# Eval.net
KiCad netlist of a schematic drawn in EAGLE
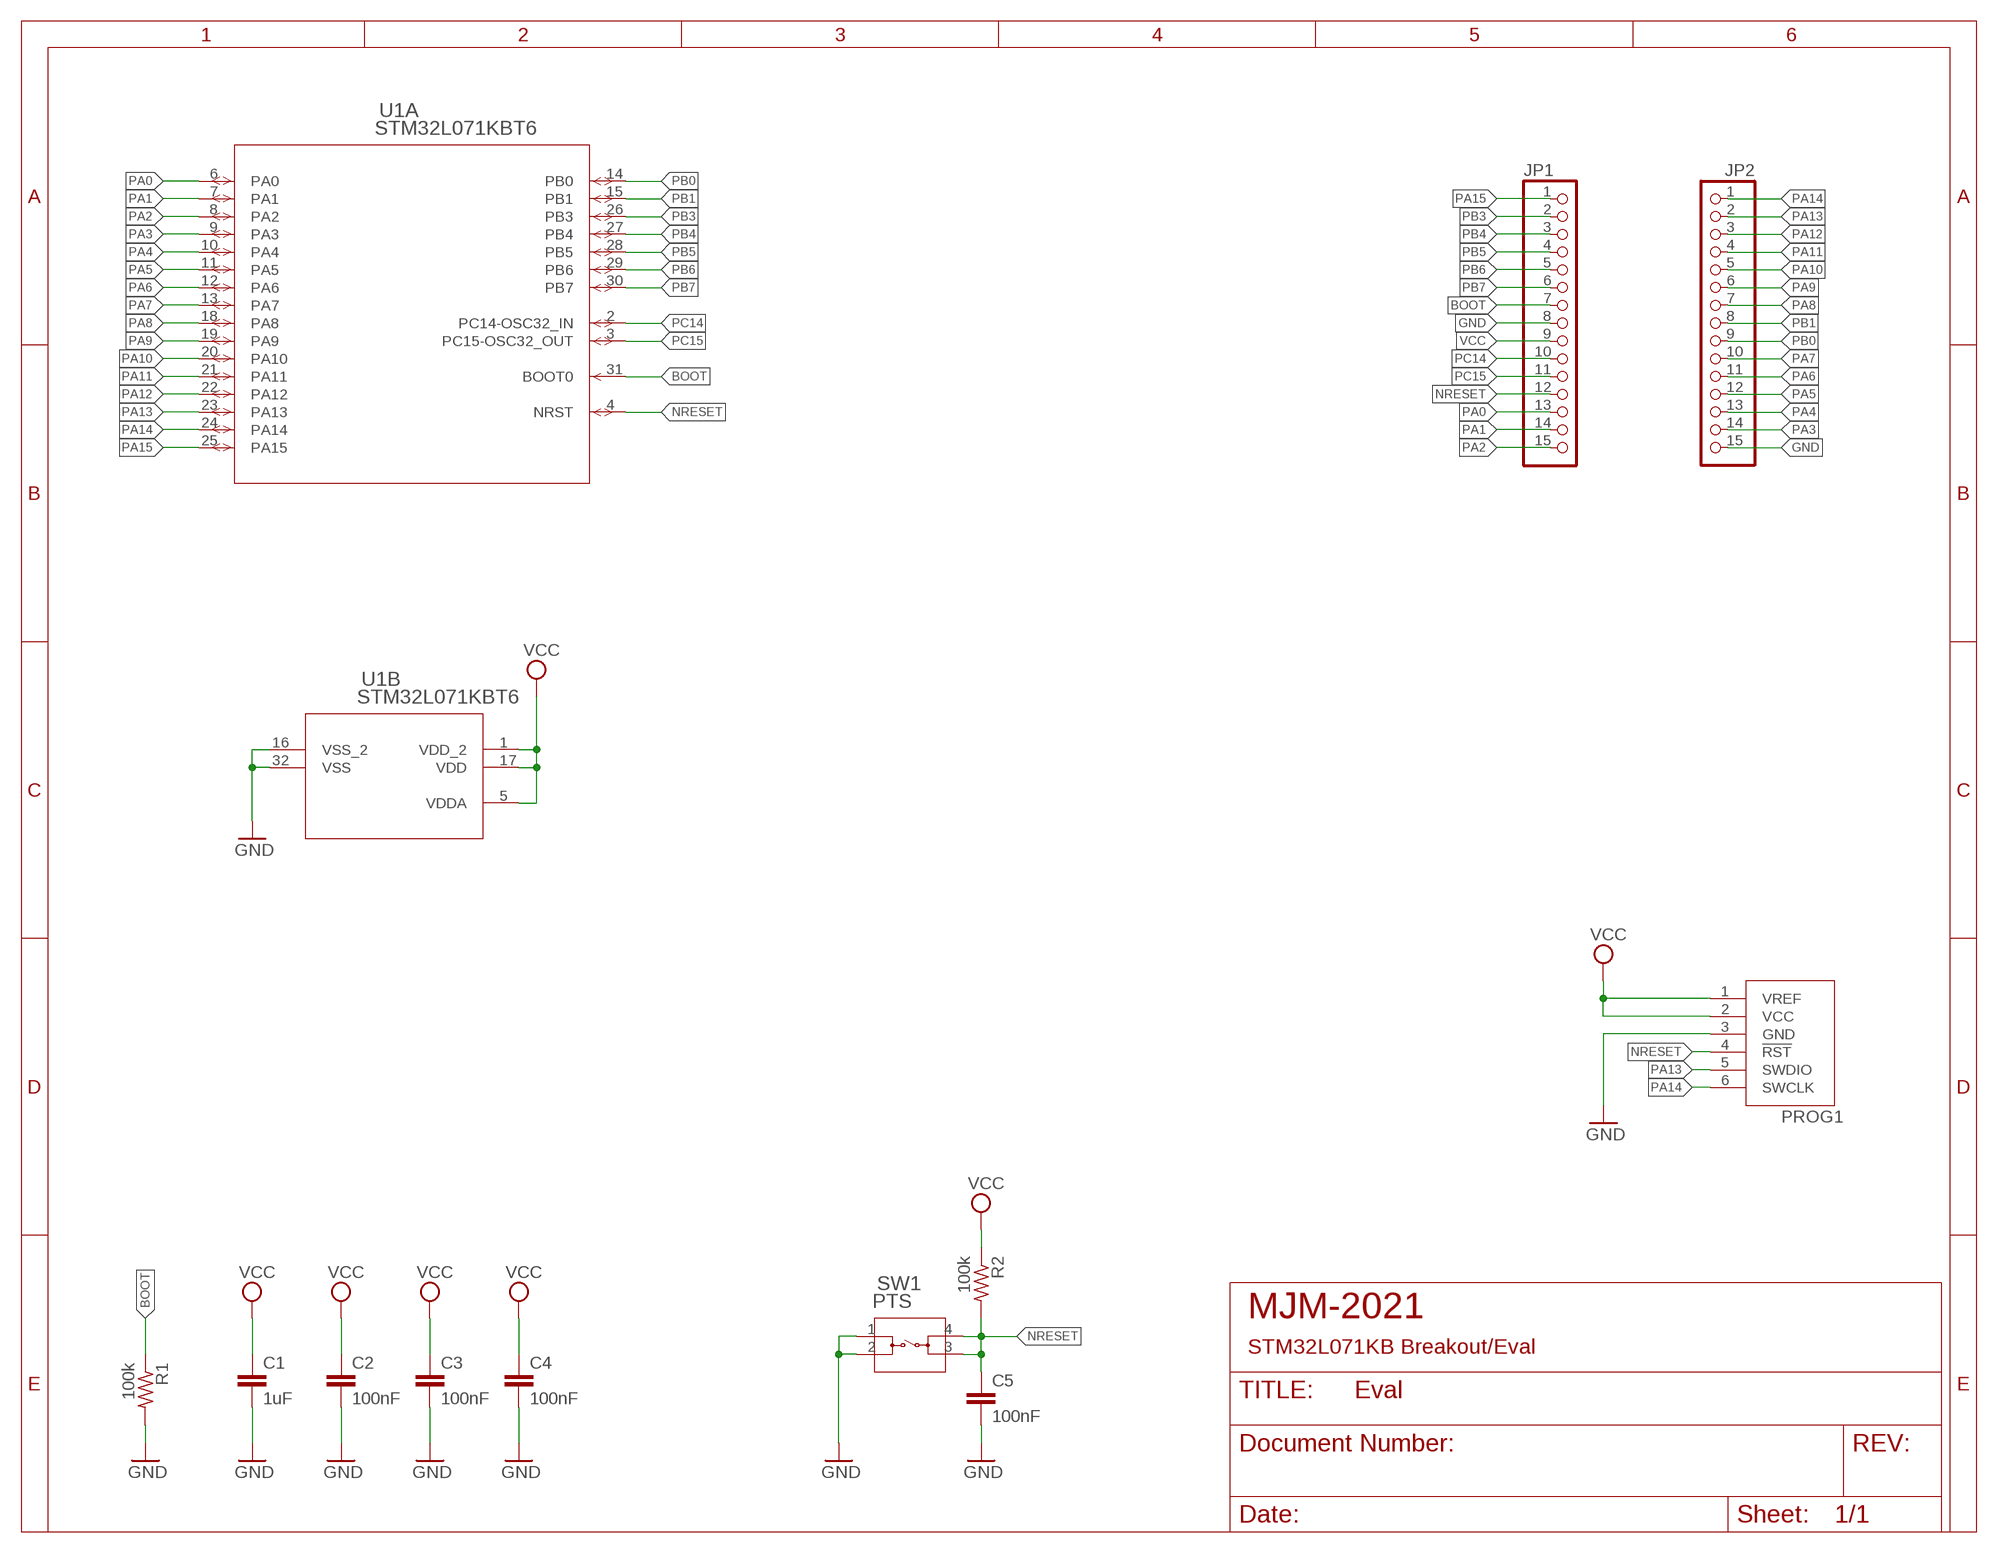
[diagram p0: schematic, sheet 1]

(export (version "E")
  (design (tool "Eeschema 10.0.6"))
  (components
    (comp (ref "C1")
      (value "1uF")
      (footprint "eagle-import:C0603")
      (libsource (lib "eagle-import") (part "C-EUC0603"))
    )
    (comp (ref "C2")
      (value "100nF")
      (footprint "eagle-import:C0603")
      (libsource (lib "eagle-import") (part "C-EUC0603"))
    )
    (comp (ref "C3")
      (value "100nF")
      (footprint "eagle-import:C0603")
      (libsource (lib "eagle-import") (part "C-EUC0603"))
    )
    (comp (ref "C4")
      (value "100nF")
      (footprint "eagle-import:C0603")
      (libsource (lib "eagle-import") (part "C-EUC0603"))
    )
    (comp (ref "C5")
      (value "100nF")
      (footprint "eagle-import:C0603")
      (libsource (lib "eagle-import") (part "C-EUC0603"))
    )
    (comp (ref "JP1")
      (value "PINHD-1X15")
      (footprint "eagle-import:1X15")
      (libsource (lib "eagle-import") (part "PINHD-1X15"))
    )
    (comp (ref "JP2")
      (value "PINHD-1X15")
      (footprint "eagle-import:1X15")
      (libsource (lib "eagle-import") (part "PINHD-1X15"))
    )
    (comp (ref "PROG1")
      (value "0532610671")
      (footprint "eagle-import:0532610671")
      (libsource (lib "eagle-import") (part "0532610671"))
    )
    (comp (ref "R1")
      (value "100k")
      (footprint "eagle-import:R0603")
      (libsource (lib "eagle-import") (part "R-US_R0603"))
    )
    (comp (ref "R2")
      (value "100k")
      (footprint "eagle-import:R0603")
      (libsource (lib "eagle-import") (part "R-US_R0603"))
    )
    (comp (ref "SW1")
      (value "PTS")
      (footprint "eagle-import:PTS_647_SN50_SMTR2_LFS-M")
      (fields
        (field (name "MANUFACTURER_PART_NUMBER") "PTS 647 SN50 SMTR2 LFS")
        (field (name "COPYRIGHT") "Copyright (C) 2018 Accelerated Designs. All rights reserved")
      )
      (libsource (lib "eagle-import") (part "PTS_647_SN50_SMTR2_LFSPTS_647_SN50_SMTR2_LFS-M"))
    )
    (comp (ref "U1")
      (value "STM32L071KBT6")
      (footprint "eagle-import:LQFP32_7X7X1P4")
      (fields (field (name "COPYRIGHT") "Copyright (C) 2018 Accelerated Designs. All rights reserved"))
      (libsource (lib "eagle-import") (part "STM32L071KBT6"))
    )
  )
  (nets
    (net (code "1") (name "BOOT") (class "Default")
      (node (ref "JP1") (pin "7") (pinfunction "7_7") (pintype "passive"))
      (node (ref "R1") (pin "1") (pinfunction "1_1") (pintype "passive"))
      (node (ref "U1") (pin "31") (pinfunction "BOOT0_31") (pintype "input"))
    )
    (net (code "2") (name "GND") (class "Default")
      (node (ref "C1") (pin "2") (pinfunction "2_2") (pintype "passive"))
      (node (ref "C2") (pin "2") (pinfunction "2_2") (pintype "passive"))
      (node (ref "C3") (pin "2") (pinfunction "2_2") (pintype "passive"))
      (node (ref "C4") (pin "2") (pinfunction "2_2") (pintype "passive"))
      (node (ref "C5") (pin "2") (pinfunction "2_2") (pintype "passive"))
      (node (ref "JP1") (pin "8") (pinfunction "8_8") (pintype "passive"))
      (node (ref "JP2") (pin "15") (pinfunction "15_15") (pintype "passive"))
      (node (ref "PROG1") (pin "3") (pinfunction "GND_3") (pintype "bidirectional"))
      (node (ref "R1") (pin "2") (pinfunction "2_2") (pintype "passive"))
      (node (ref "SW1") (pin "1") (pinfunction "1_1") (pintype "passive"))
      (node (ref "SW1") (pin "2") (pinfunction "2_2") (pintype "passive"))
      (node (ref "U1") (pin "16") (pinfunction "VSS_2_16") (pintype "power_in"))
      (node (ref "U1") (pin "32") (pinfunction "VSS_32") (pintype "power_in"))
    )
    (net (code "3") (name "NRESET") (class "Default")
      (node (ref "C5") (pin "1") (pinfunction "1_1") (pintype "passive"))
      (node (ref "JP1") (pin "12") (pinfunction "12_12") (pintype "passive"))
      (node (ref "PROG1") (pin "4") (pinfunction "~{RST}_4") (pintype "bidirectional"))
      (node (ref "R2") (pin "2") (pinfunction "2_2") (pintype "passive"))
      (node (ref "SW1") (pin "3") (pinfunction "3_3") (pintype "passive"))
      (node (ref "SW1") (pin "4") (pinfunction "4_4") (pintype "passive"))
      (node (ref "U1") (pin "4") (pinfunction "NRST_4") (pintype "bidirectional"))
    )
    (net (code "4") (name "PA0") (class "Default")
      (node (ref "JP1") (pin "13") (pinfunction "13_13") (pintype "passive"))
      (node (ref "U1") (pin "6") (pinfunction "PA0_6") (pintype "bidirectional"))
    )
    (net (code "5") (name "PA1") (class "Default")
      (node (ref "JP1") (pin "14") (pinfunction "14_14") (pintype "passive"))
      (node (ref "U1") (pin "7") (pinfunction "PA1_7") (pintype "bidirectional"))
    )
    (net (code "6") (name "PA2") (class "Default")
      (node (ref "JP1") (pin "15") (pinfunction "15_15") (pintype "passive"))
      (node (ref "U1") (pin "8") (pinfunction "PA2_8") (pintype "bidirectional"))
    )
    (net (code "7") (name "PA3") (class "Default")
      (node (ref "JP2") (pin "14") (pinfunction "14_14") (pintype "passive"))
      (node (ref "U1") (pin "9") (pinfunction "PA3_9") (pintype "bidirectional"))
    )
    (net (code "8") (name "PA4") (class "Default")
      (node (ref "JP2") (pin "13") (pinfunction "13_13") (pintype "passive"))
      (node (ref "U1") (pin "10") (pinfunction "PA4_10") (pintype "bidirectional"))
    )
    (net (code "9") (name "PA5") (class "Default")
      (node (ref "JP2") (pin "12") (pinfunction "12_12") (pintype "passive"))
      (node (ref "U1") (pin "11") (pinfunction "PA5_11") (pintype "bidirectional"))
    )
    (net (code "10") (name "PA6") (class "Default")
      (node (ref "JP2") (pin "11") (pinfunction "11_11") (pintype "passive"))
      (node (ref "U1") (pin "12") (pinfunction "PA6_12") (pintype "bidirectional"))
    )
    (net (code "11") (name "PA7") (class "Default")
      (node (ref "JP2") (pin "10") (pinfunction "10_10") (pintype "passive"))
      (node (ref "U1") (pin "13") (pinfunction "PA7_13") (pintype "bidirectional"))
    )
    (net (code "12") (name "PA8") (class "Default")
      (node (ref "JP2") (pin "7") (pinfunction "7_7") (pintype "passive"))
      (node (ref "U1") (pin "18") (pinfunction "PA8_18") (pintype "bidirectional"))
    )
    (net (code "13") (name "PA9") (class "Default")
      (node (ref "JP2") (pin "6") (pinfunction "6_6") (pintype "passive"))
      (node (ref "U1") (pin "19") (pinfunction "PA9_19") (pintype "bidirectional"))
    )
    (net (code "14") (name "PA10") (class "Default")
      (node (ref "JP2") (pin "5") (pinfunction "5_5") (pintype "passive"))
      (node (ref "U1") (pin "20") (pinfunction "PA10_20") (pintype "bidirectional"))
    )
    (net (code "15") (name "PA11") (class "Default")
      (node (ref "JP2") (pin "4") (pinfunction "4_4") (pintype "passive"))
      (node (ref "U1") (pin "21") (pinfunction "PA11_21") (pintype "bidirectional"))
    )
    (net (code "16") (name "PA12") (class "Default")
      (node (ref "JP2") (pin "3") (pinfunction "3_3") (pintype "passive"))
      (node (ref "U1") (pin "22") (pinfunction "PA12_22") (pintype "bidirectional"))
    )
    (net (code "17") (name "PA13") (class "Default")
      (node (ref "JP2") (pin "2") (pinfunction "2_2") (pintype "passive"))
      (node (ref "PROG1") (pin "5") (pinfunction "SWDIO_5") (pintype "bidirectional"))
      (node (ref "U1") (pin "23") (pinfunction "PA13_23") (pintype "bidirectional"))
    )
    (net (code "18") (name "PA14") (class "Default")
      (node (ref "JP2") (pin "1") (pinfunction "1_1") (pintype "passive"))
      (node (ref "PROG1") (pin "6") (pinfunction "SWCLK_6") (pintype "bidirectional"))
      (node (ref "U1") (pin "24") (pinfunction "PA14_24") (pintype "bidirectional"))
    )
    (net (code "19") (name "PA15") (class "Default")
      (node (ref "JP1") (pin "1") (pinfunction "1_1") (pintype "passive"))
      (node (ref "U1") (pin "25") (pinfunction "PA15_25") (pintype "bidirectional"))
    )
    (net (code "20") (name "PB0") (class "Default")
      (node (ref "JP2") (pin "9") (pinfunction "9_9") (pintype "passive"))
      (node (ref "U1") (pin "14") (pinfunction "PB0_14") (pintype "bidirectional"))
    )
    (net (code "21") (name "PB1") (class "Default")
      (node (ref "JP2") (pin "8") (pinfunction "8_8") (pintype "passive"))
      (node (ref "U1") (pin "15") (pinfunction "PB1_15") (pintype "bidirectional"))
    )
    (net (code "22") (name "PB3") (class "Default")
      (node (ref "JP1") (pin "2") (pinfunction "2_2") (pintype "passive"))
      (node (ref "U1") (pin "26") (pinfunction "PB3_26") (pintype "bidirectional"))
    )
    (net (code "23") (name "PB4") (class "Default")
      (node (ref "JP1") (pin "3") (pinfunction "3_3") (pintype "passive"))
      (node (ref "U1") (pin "27") (pinfunction "PB4_27") (pintype "bidirectional"))
    )
    (net (code "24") (name "PB5") (class "Default")
      (node (ref "JP1") (pin "4") (pinfunction "4_4") (pintype "passive"))
      (node (ref "U1") (pin "28") (pinfunction "PB5_28") (pintype "bidirectional"))
    )
    (net (code "25") (name "PB6") (class "Default")
      (node (ref "JP1") (pin "5") (pinfunction "5_5") (pintype "passive"))
      (node (ref "U1") (pin "29") (pinfunction "PB6_29") (pintype "bidirectional"))
    )
    (net (code "26") (name "PB7") (class "Default")
      (node (ref "JP1") (pin "6") (pinfunction "6_6") (pintype "passive"))
      (node (ref "U1") (pin "30") (pinfunction "PB7_30") (pintype "bidirectional"))
    )
    (net (code "27") (name "PC14") (class "Default")
      (node (ref "JP1") (pin "10") (pinfunction "10_10") (pintype "passive"))
      (node (ref "U1") (pin "2") (pinfunction "PC14-OSC32_IN_2") (pintype "bidirectional"))
    )
    (net (code "28") (name "PC15") (class "Default")
      (node (ref "JP1") (pin "11") (pinfunction "11_11") (pintype "passive"))
      (node (ref "U1") (pin "3") (pinfunction "PC15-OSC32_OUT_3") (pintype "bidirectional"))
    )
    (net (code "29") (name "VCC") (class "Default")
      (node (ref "C1") (pin "1") (pinfunction "1_1") (pintype "passive"))
      (node (ref "C2") (pin "1") (pinfunction "1_1") (pintype "passive"))
      (node (ref "C3") (pin "1") (pinfunction "1_1") (pintype "passive"))
      (node (ref "C4") (pin "1") (pinfunction "1_1") (pintype "passive"))
      (node (ref "JP1") (pin "9") (pinfunction "9_9") (pintype "passive"))
      (node (ref "PROG1") (pin "1") (pinfunction "VREF_1") (pintype "bidirectional"))
      (node (ref "PROG1") (pin "2") (pinfunction "VCC_2") (pintype "bidirectional"))
      (node (ref "R2") (pin "1") (pinfunction "1_1") (pintype "passive"))
      (node (ref "U1") (pin "1") (pinfunction "VDD_2_1") (pintype "power_in"))
      (node (ref "U1") (pin "17") (pinfunction "VDD_17") (pintype "power_in"))
      (node (ref "U1") (pin "5") (pinfunction "VDDA_5") (pintype "power_in"))
    )
  )
)
